# 6coils-1-discrete.net
KiCad netlist of a schematic drawn in EasyEDA
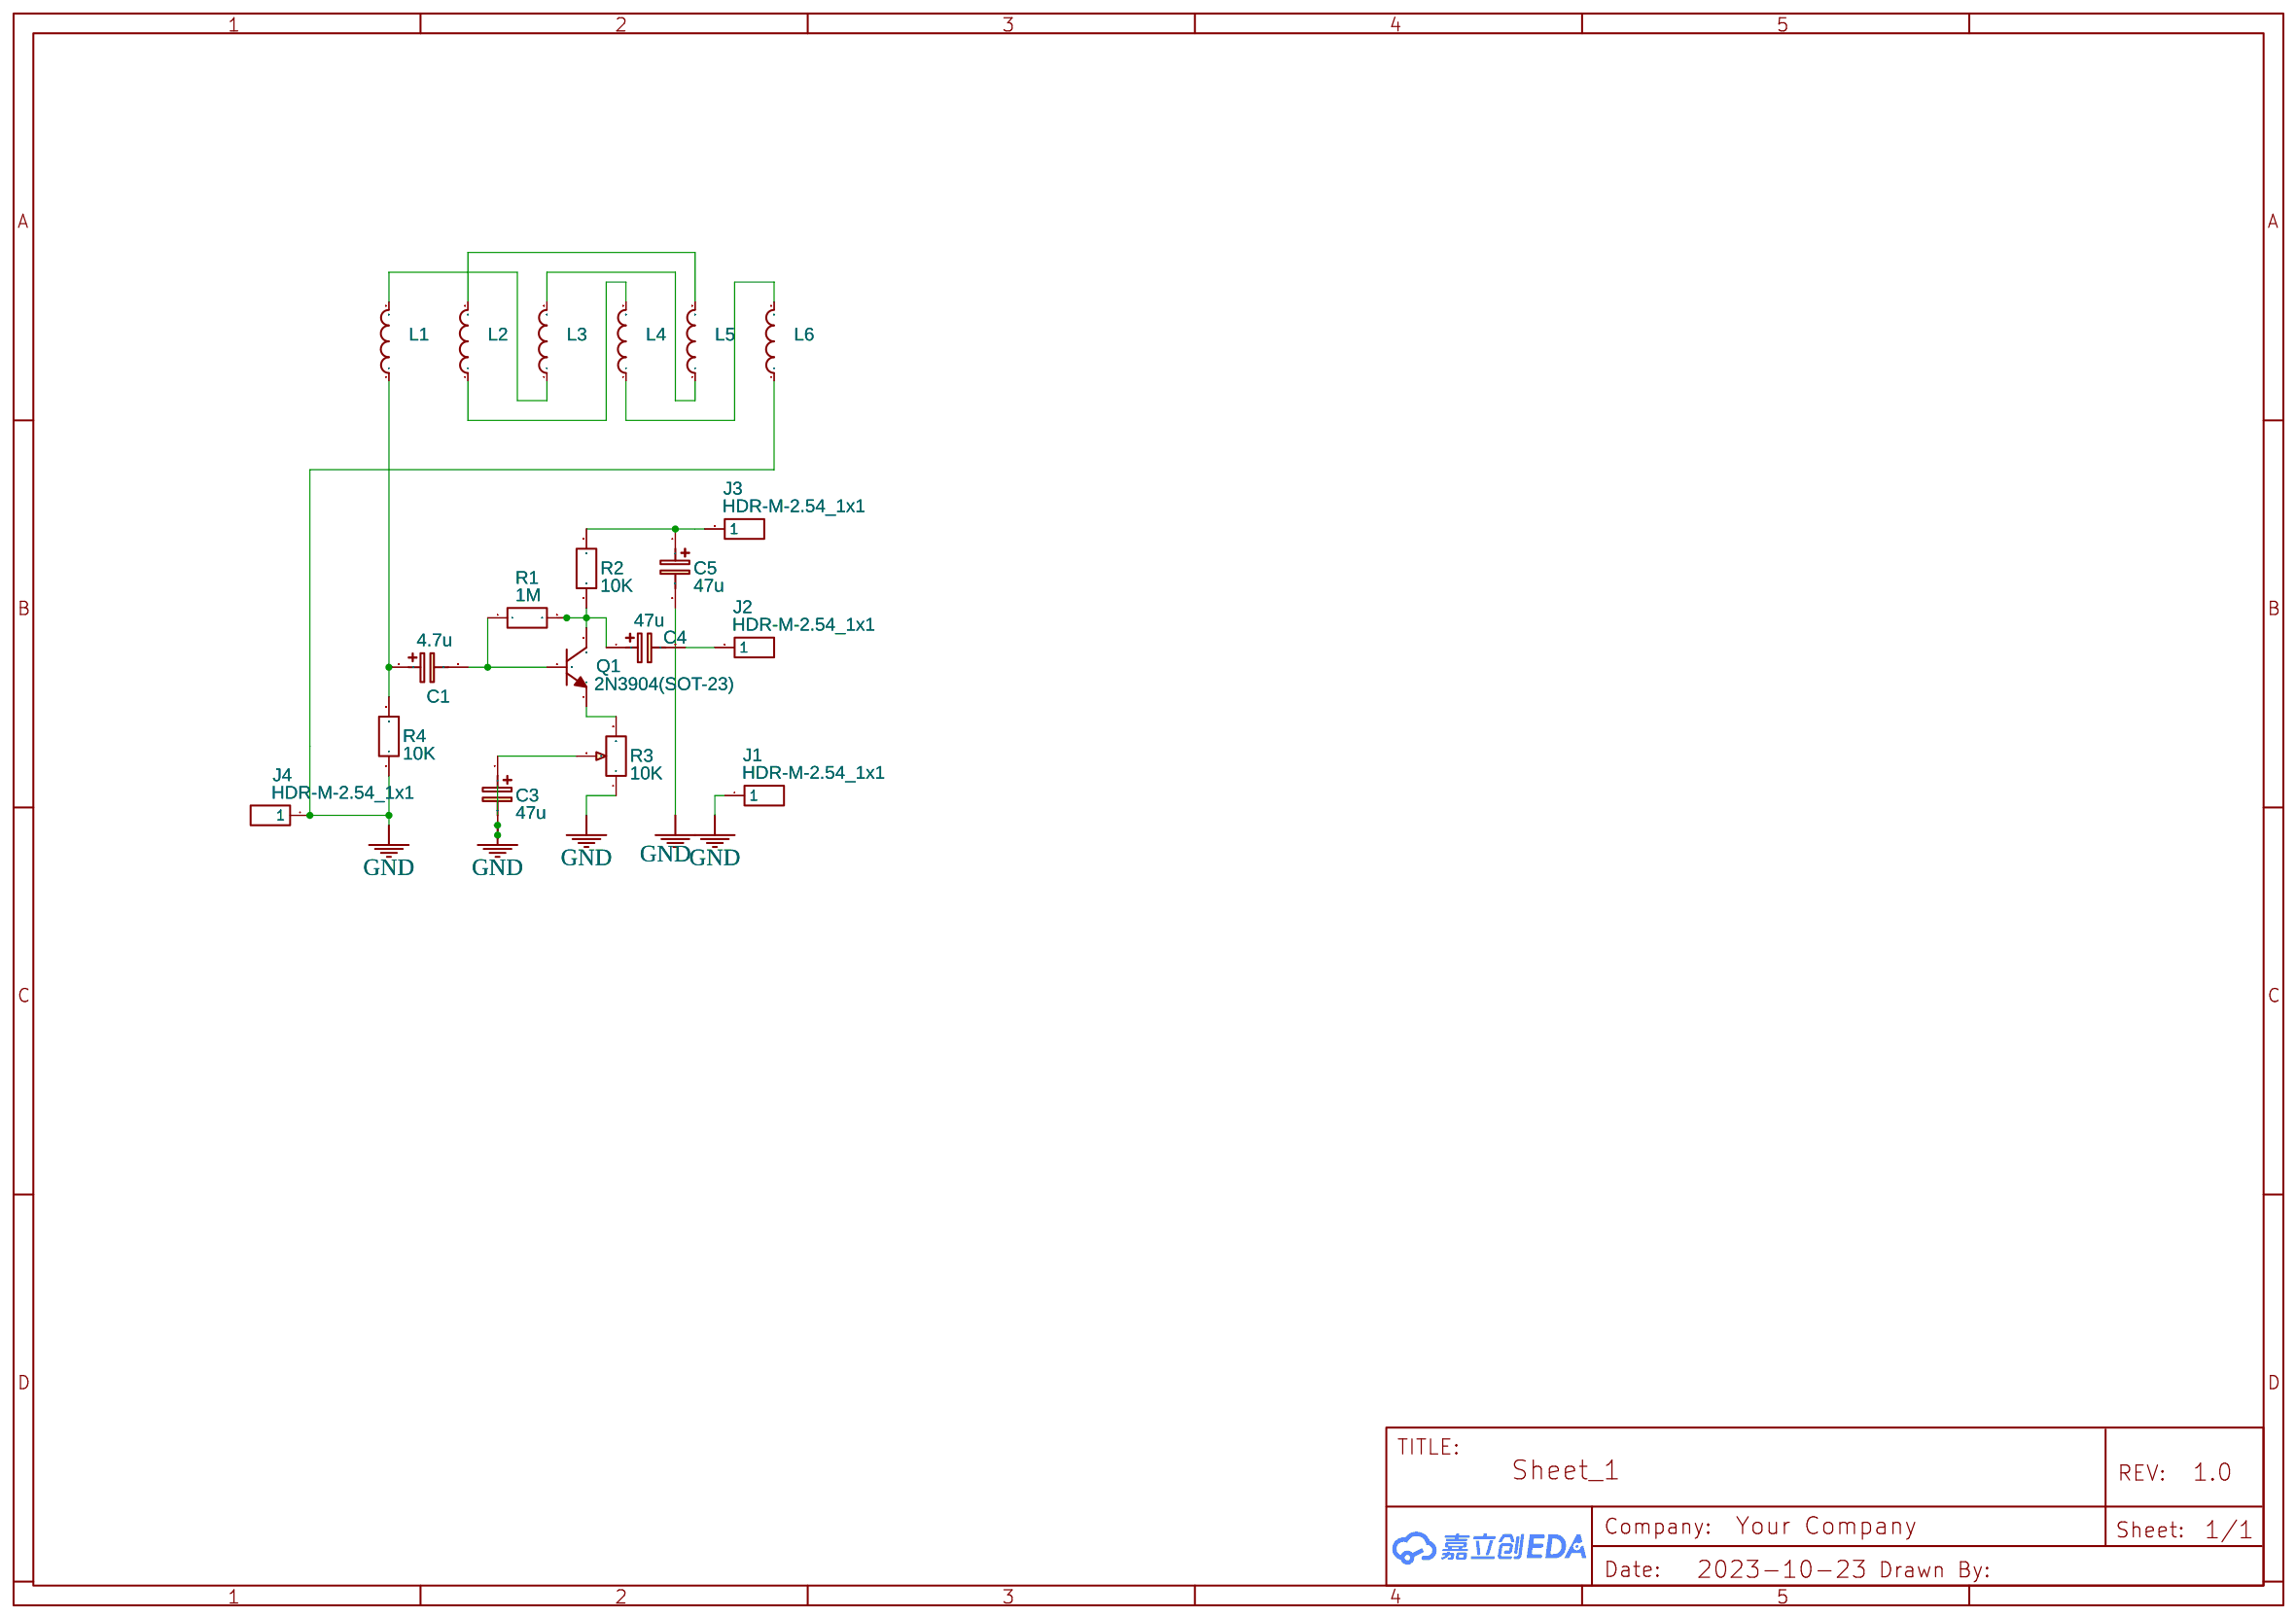
[diagram p0: schematic sheet]

(export (version "E")
  (design (tool "Eeschema 10.0.6"))
  (components
    (comp (ref "C1") (value "4.7u") (libsource (lib "") (part "C_Tan_SMD_A_EU_2")))
    (comp (ref "C3") (value "47u") (libsource (lib "") (part "C_Tan_SMD_A_EU")))
    (comp (ref "C4") (value "47u") (libsource (lib "") (part "C_Tan_SMD_A_EU_1")))
    (comp (ref "C5") (value "47u") (libsource (lib "") (part "C_Tan_SMD_A_EU_3")))
    (comp (ref "J1")
      (value "HDR-M-2.54_1x1")
      (fields (field (name "BOM_Supplier Part") "C81276"))
      (libsource (lib "") (part "HDR-M-2.54_1x1"))
    )
    (comp (ref "J2")
      (value "HDR-M-2.54_1x1")
      (fields (field (name "BOM_Supplier Part") "C81276"))
      (libsource (lib "") (part "HDR-M-2.54_1x1"))
    )
    (comp (ref "J3")
      (value "HDR-M-2.54_1x1")
      (fields (field (name "BOM_Supplier Part") "C81276"))
      (libsource (lib "") (part "HDR-M-2.54_1x1"))
    )
    (comp (ref "J4")
      (value "HDR-M-2.54_1x1")
      (fields (field (name "BOM_Supplier Part") "C81276"))
      (libsource (lib "") (part "HDR-M-2.54_1x1_1"))
    )
    (comp (ref "L1")
      (value "INDUCTOR_SMD:L_COILCRAFT_XXL4040")
      (fields (field (name "Manufacturer Part") "Inductor_SMD:L_Coilcraft_XxL4040"))
      (libsource (lib "") (part "INDUCTOR_SMD{colon}L_COILCRAFT_XXL4040_1"))
    )
    (comp (ref "L2")
      (value "INDUCTOR_SMD:L_COILCRAFT_XXL4040")
      (fields (field (name "Manufacturer Part") "Inductor_SMD:L_Coilcraft_XxL4040"))
      (libsource (lib "") (part "INDUCTOR_SMD{colon}L_COILCRAFT_XXL4040_1"))
    )
    (comp (ref "L3")
      (value "INDUCTOR_SMD:L_COILCRAFT_XXL4040")
      (fields (field (name "Manufacturer Part") "Inductor_SMD:L_Coilcraft_XxL4040"))
      (libsource (lib "") (part "INDUCTOR_SMD{colon}L_COILCRAFT_XXL4040"))
    )
    (comp (ref "L4")
      (value "INDUCTOR_SMD:L_COILCRAFT_XXL4040")
      (fields (field (name "Manufacturer Part") "Inductor_SMD:L_Coilcraft_XxL4040"))
      (libsource (lib "") (part "INDUCTOR_SMD{colon}L_COILCRAFT_XXL4040"))
    )
    (comp (ref "L5")
      (value "INDUCTOR_SMD:L_COILCRAFT_XXL4040")
      (fields (field (name "Manufacturer Part") "Inductor_SMD:L_Coilcraft_XxL4040"))
      (libsource (lib "") (part "INDUCTOR_SMD{colon}L_COILCRAFT_XXL4040"))
    )
    (comp (ref "L6")
      (value "INDUCTOR_SMD:L_COILCRAFT_XXL4040")
      (fields (field (name "Manufacturer Part") "Inductor_SMD:L_Coilcraft_XxL4040"))
      (libsource (lib "") (part "INDUCTOR_SMD{colon}L_COILCRAFT_XXL4040"))
    )
    (comp (ref "Q1")
      (value "2N3904(SOT-23)")
      (fields
        (field (name "BOM_Manufacturer Part") "2n3904S-RTK/PS")
        (field (name "BOM_Supplier Part") "C18536")
      )
      (libsource (lib "") (part "2N3904(SOT-23)"))
    )
    (comp (ref "R1") (value "1M") (libsource (lib "") (part "R_0603_EU")))
    (comp (ref "R2") (value "10K") (libsource (lib "") (part "R_0603_EU_1")))
    (comp (ref "R3")
      (value "10K")
      (fields (field (name "Manufacturer Part") "RM063-103 10K") (field (name "Manufacturer") "JML"))
      (libsource (lib "") (part "RM063-103 10K"))
    )
    (comp (ref "R4") (value "10K") (libsource (lib "") (part "R_0603_EU_1")))
  )
  (nets
    (net (code "1") (name "GND") (class "Default")
      (node (ref "C3") (pin "2") (pinfunction "2_2") (pintype "unspecified"))
      (node (ref "C5") (pin "2") (pinfunction "2_2") (pintype "unspecified"))
      (node (ref "J1") (pin "1") (pinfunction "1_1") (pintype "input"))
      (node (ref "J4") (pin "1") (pinfunction "1_1") (pintype "input"))
      (node (ref "L6") (pin "1") (pinfunction "1_1") (pintype "unspecified"))
      (node (ref "R3") (pin "1") (pinfunction "1_1") (pintype "input"))
      (node (ref "R4") (pin "1") (pinfunction "1_1") (pintype "unspecified"))
    )
    (net (code "2") (name "Net-(C1-Pad1)") (class "Default")
      (node (ref "C1") (pin "1") (pinfunction "1_1") (pintype "unspecified"))
      (node (ref "L1") (pin "1") (pinfunction "1_1") (pintype "unspecified"))
      (node (ref "R4") (pin "2") (pinfunction "2_2") (pintype "unspecified"))
    )
    (net (code "3") (name "Net-(C3-Pad1)") (class "Default")
      (node (ref "C3") (pin "1") (pinfunction "1_1") (pintype "unspecified"))
      (node (ref "R3") (pin "2") (pinfunction "2_2") (pintype "input"))
    )
    (net (code "4") (name "Net-(C4-Pad2)") (class "Default")
      (node (ref "C4") (pin "2") (pinfunction "2_2") (pintype "unspecified"))
      (node (ref "J2") (pin "1") (pinfunction "1_1") (pintype "input"))
    )
    (net (code "5") (name "Net-(C5-Pad1)") (class "Default")
      (node (ref "C5") (pin "1") (pinfunction "1_1") (pintype "unspecified"))
      (node (ref "J3") (pin "1") (pinfunction "1_1") (pintype "input"))
      (node (ref "R2") (pin "2") (pinfunction "2_2") (pintype "unspecified"))
    )
    (net (code "6") (name "Net-(L1-Pad2)") (class "Default")
      (node (ref "L1") (pin "2") (pinfunction "2_2") (pintype "unspecified"))
      (node (ref "L3") (pin "1") (pinfunction "1_1") (pintype "unspecified"))
    )
    (net (code "7") (name "Net-(L2-Pad1)") (class "Default")
      (node (ref "L2") (pin "1") (pinfunction "1_1") (pintype "unspecified"))
      (node (ref "L4") (pin "2") (pinfunction "2_2") (pintype "unspecified"))
    )
    (net (code "8") (name "Net-(L2-Pad2)") (class "Default")
      (node (ref "L2") (pin "2") (pinfunction "2_2") (pintype "unspecified"))
      (node (ref "L5") (pin "2") (pinfunction "2_2") (pintype "unspecified"))
    )
    (net (code "9") (name "Net-(L3-Pad2)") (class "Default")
      (node (ref "L3") (pin "2") (pinfunction "2_2") (pintype "unspecified"))
      (node (ref "L5") (pin "1") (pinfunction "1_1") (pintype "unspecified"))
    )
    (net (code "10") (name "Net-(L4-Pad1)") (class "Default")
      (node (ref "L4") (pin "1") (pinfunction "1_1") (pintype "unspecified"))
      (node (ref "L6") (pin "2") (pinfunction "2_2") (pintype "unspecified"))
    )
    (net (code "11") (name "Net-(Q1-B)") (class "Default")
      (node (ref "C1") (pin "2") (pinfunction "2_2") (pintype "unspecified"))
      (node (ref "Q1") (pin "2") (pinfunction "B_2") (pintype "input"))
      (node (ref "R1") (pin "1") (pinfunction "1_1") (pintype "unspecified"))
    )
    (net (code "12") (name "Net-(Q1-C)") (class "Default")
      (node (ref "C4") (pin "1") (pinfunction "1_1") (pintype "unspecified"))
      (node (ref "Q1") (pin "3") (pinfunction "C_3") (pintype "input"))
      (node (ref "R1") (pin "2") (pinfunction "2_2") (pintype "unspecified"))
      (node (ref "R2") (pin "1") (pinfunction "1_1") (pintype "unspecified"))
    )
    (net (code "13") (name "Net-(Q1-E)") (class "Default")
      (node (ref "Q1") (pin "1") (pinfunction "E_1") (pintype "input"))
      (node (ref "R3") (pin "3") (pinfunction "3_3") (pintype "input"))
    )
  )
)
